# ProDoc_USB-C_Advanced_Power_Supply.net
KiCad netlist of a schematic drawn in EasyEDA Pro
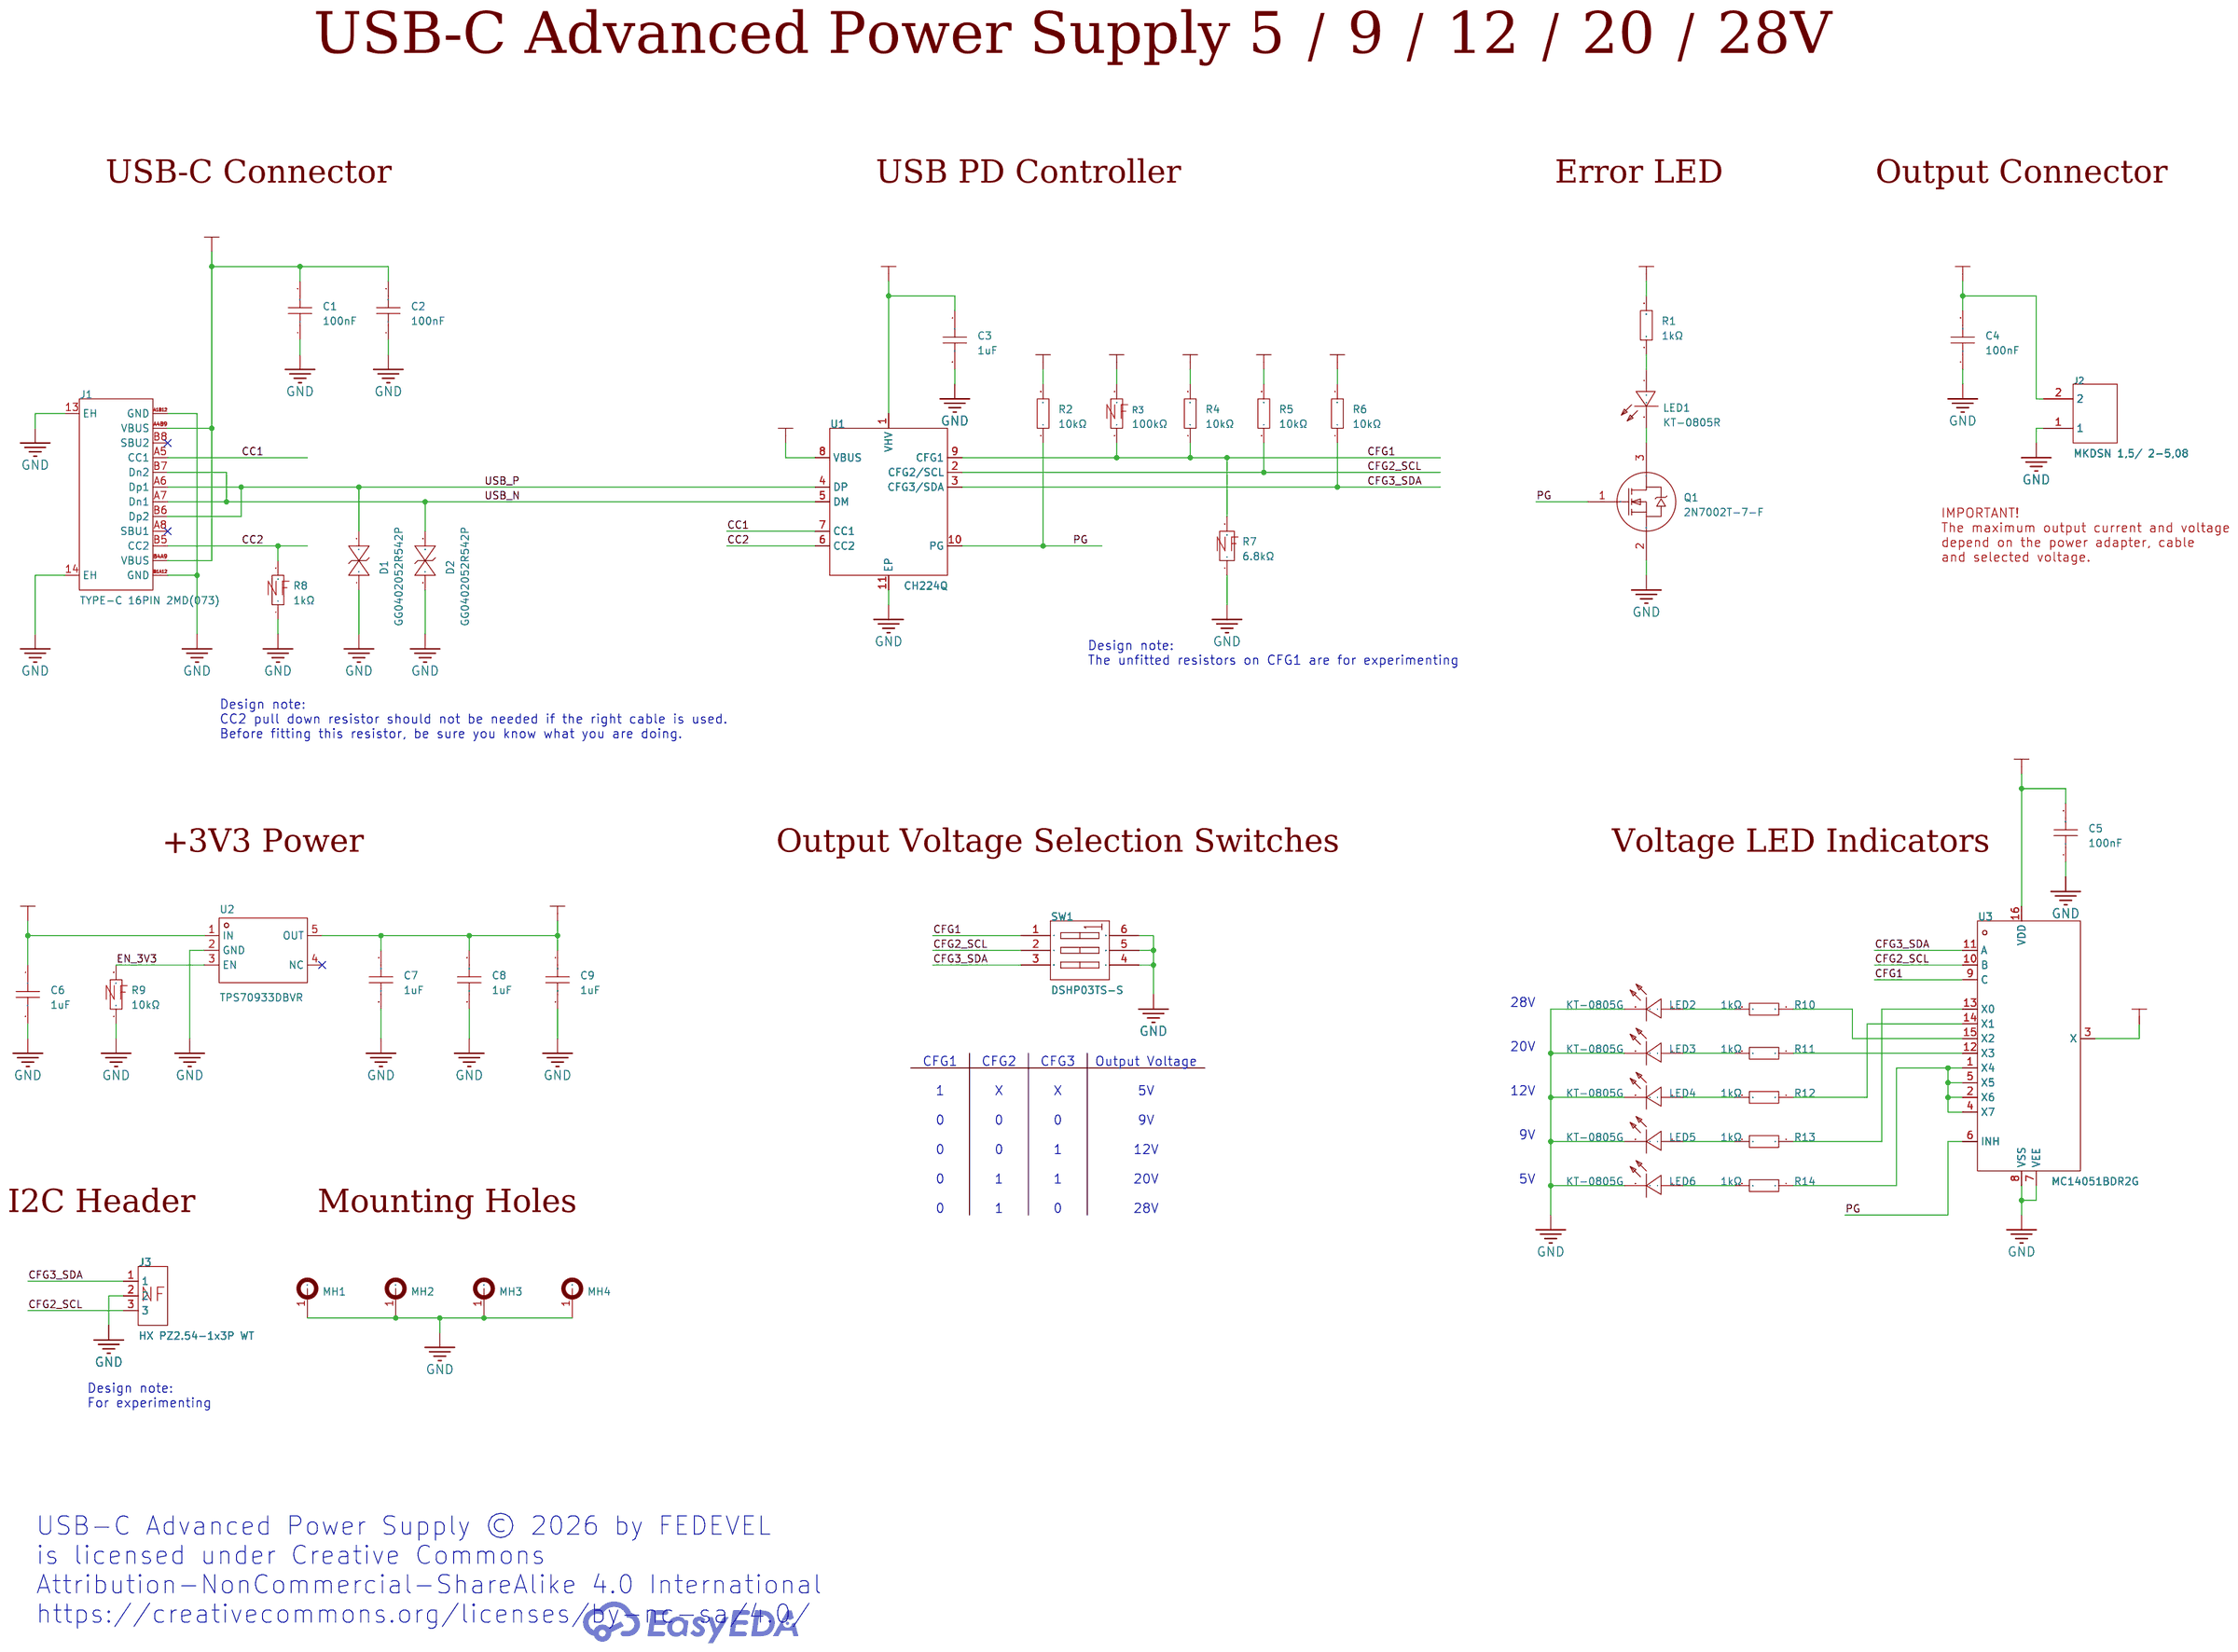
[diagram p0: schematic sheet]

(export (version "E")
  (design (tool "Eeschema 10.0.6"))
  (components
    (comp (ref "C1")
      (value "100nF")
      (footprint "easyedapro:C0402")
      (description "Capacitance:100nF Tolerance:±10% Tolerance:±10% Voltage Rating:50V Temperature Coefficient:X7R")
      (fields
        (field (name "Manufacturer Part") "CL05B104KB54PNC")
        (field (name "Manufacturer") "SAMSUNG(三星)")
      )
      (libsource (lib "easyedapro") (part "CL05B104KB54PNC"))
    )
    (comp (ref "C2")
      (value "100nF")
      (footprint "easyedapro:C0402")
      (description "Capacitance:100nF Tolerance:±10% Tolerance:±10% Voltage Rating:50V Temperature Coefficient:X7R")
      (fields
        (field (name "Manufacturer Part") "CL05B104KB54PNC")
        (field (name "Manufacturer") "SAMSUNG(三星)")
      )
      (libsource (lib "easyedapro") (part "CL05B104KB54PNC"))
    )
    (comp (ref "C3")
      (value "1uF")
      (footprint "easyedapro:C0603")
      (description "Capacitance:1uF Tolerance:±10% Tolerance:±10% Voltage Rating:50V Temperature Coefficient:X7R")
      (fields
        (field (name "Manufacturer Part") "CL10B105KB8NQNC")
        (field (name "Manufacturer") "SAMSUNG(三星)")
      )
      (libsource (lib "easyedapro") (part "CL10B105KB8NQNC"))
    )
    (comp (ref "C4")
      (value "100nF")
      (footprint "easyedapro:C0402")
      (description "Capacitance:100nF Tolerance:±10% Tolerance:±10% Voltage Rating:50V Temperature Coefficient:X7R")
      (fields
        (field (name "Manufacturer Part") "CL05B104KB54PNC")
        (field (name "Manufacturer") "SAMSUNG(三星)")
      )
      (libsource (lib "easyedapro") (part "CL05B104KB54PNC"))
    )
    (comp (ref "C5")
      (value "100nF")
      (footprint "easyedapro:C0402")
      (description "Capacitance:100nF Tolerance:±10% Tolerance:±10% Voltage Rating:50V Temperature Coefficient:X7R")
      (fields
        (field (name "Manufacturer Part") "CL05B104KB54PNC")
        (field (name "Manufacturer") "SAMSUNG(三星)")
      )
      (libsource (lib "easyedapro") (part "CL05B104KB54PNC"))
    )
    (comp (ref "C6")
      (value "1uF")
      (footprint "easyedapro:C0603")
      (description "Capacitance:1uF Tolerance:±10% Tolerance:±10% Voltage Rating:50V Temperature Coefficient:X7R")
      (fields
        (field (name "Manufacturer Part") "CL10B105KB8NQNC")
        (field (name "Manufacturer") "SAMSUNG(三星)")
      )
      (libsource (lib "easyedapro") (part "CL10B105KB8NQNC"))
    )
    (comp (ref "C7")
      (value "1uF")
      (footprint "easyedapro:C0603")
      (description "Capacitance:1uF Tolerance:±10% Tolerance:±10% Voltage Rating:50V Temperature Coefficient:X7R")
      (fields
        (field (name "Manufacturer Part") "CL10B105KB8NQNC")
        (field (name "Manufacturer") "SAMSUNG(三星)")
      )
      (libsource (lib "easyedapro") (part "CL10B105KB8NQNC"))
    )
    (comp (ref "C8")
      (value "1uF")
      (footprint "easyedapro:C0603")
      (description "Capacitance:1uF Tolerance:±10% Tolerance:±10% Voltage Rating:50V Temperature Coefficient:X7R")
      (fields
        (field (name "Manufacturer Part") "CL10B105KB8NQNC")
        (field (name "Manufacturer") "SAMSUNG(三星)")
      )
      (libsource (lib "easyedapro") (part "CL10B105KB8NQNC"))
    )
    (comp (ref "C9")
      (value "1uF")
      (footprint "easyedapro:C0603")
      (description "Capacitance:1uF Tolerance:±10% Tolerance:±10% Voltage Rating:50V Temperature Coefficient:X7R")
      (fields
        (field (name "Manufacturer Part") "CL10B105KB8NQNC")
        (field (name "Manufacturer") "SAMSUNG(三星)")
      )
      (libsource (lib "easyedapro") (part "CL10B105KB8NQNC"))
    )
    (comp (ref "D1")
      (value "GG0402052R542P")
      (footprint "easyedapro:D0402-BI")
      (fields (field (name "Manufacturer") "Kyocera AVX"))
      (libsource (lib "easyedapro") (part "GG0402052R542P"))
    )
    (comp (ref "D2")
      (value "GG0402052R542P")
      (footprint "easyedapro:D0402-BI")
      (fields (field (name "Manufacturer") "Kyocera AVX"))
      (libsource (lib "easyedapro") (part "GG0402052R542P"))
    )
    (comp (ref "J1")
      (value "TYPE-C 16PIN 2MD(073)")
      (footprint "easyedapro:USB-C-SMD_TYPE-C-16PIN-2MD-073")
      (fields (field (name "Manufacturer") "SHOU HAN(首韩)"))
      (libsource (lib "easyedapro") (part "TYPE-C 16PIN 2MD(073)"))
    )
    (comp (ref "J2")
      (value "MKDSN 1,5/ 2-5,08")
      (footprint "easyedapro:CONN-TH_2P-P5.08_1729128")
      (fields (field (name "Manufacturer") "Phoenix Contact(菲尼克斯)"))
      (libsource (lib "easyedapro") (part "MKDSN 1,5/ 2-5,08"))
    )
    (comp (ref "J3")
      (value "HX PZ2.54-1x3P WT")
      (footprint "easyedapro:HDR-SMD_3P-P2.54-H-M_KH-2.54PH-1X3P-L13.5-WT")
      (fields (field (name "Manufacturer") "hanxia(韩下)"))
      (libsource (lib "easyedapro") (part "HX PZ2.54-1X3P WT"))
    )
    (comp (ref "LED1")
      (value "KT-0805R")
      (footprint "easyedapro:LED0805-R-RD")
      (fields (field (name "Manufacturer") "KENTO"))
      (libsource (lib "easyedapro") (part "E6C0805UR"))
    )
    (comp (ref "LED2")
      (value "KT-0805G")
      (footprint "easyedapro:LED0805-R-RD")
      (fields (field (name "Manufacturer") "KENTO"))
      (libsource (lib "easyedapro") (part "0805G (Green)"))
    )
    (comp (ref "LED3")
      (value "KT-0805G")
      (footprint "easyedapro:LED0805-R-RD")
      (fields (field (name "Manufacturer") "KENTO"))
      (libsource (lib "easyedapro") (part "0805G (Green)"))
    )
    (comp (ref "LED4")
      (value "KT-0805G")
      (footprint "easyedapro:LED0805-R-RD")
      (fields (field (name "Manufacturer") "KENTO"))
      (libsource (lib "easyedapro") (part "0805G (Green)"))
    )
    (comp (ref "LED5")
      (value "KT-0805G")
      (footprint "easyedapro:LED0805-R-RD")
      (fields (field (name "Manufacturer") "KENTO"))
      (libsource (lib "easyedapro") (part "0805G (Green)"))
    )
    (comp (ref "LED6")
      (value "KT-0805G")
      (footprint "easyedapro:LED0805-R-RD")
      (fields (field (name "Manufacturer") "KENTO"))
      (libsource (lib "easyedapro") (part "0805G (Green)"))
    )
    (comp (ref "MH1")
      (value "~")
      (footprint "easyedapro:MH_7.5MMx2.7MM")
      (libsource (lib "easyedapro") (part "MH_7.5MMx2.7MM"))
    )
    (comp (ref "MH2")
      (value "~")
      (footprint "easyedapro:MH_7.5MMx2.7MM")
      (libsource (lib "easyedapro") (part "MH_7.5MMx2.7MM"))
    )
    (comp (ref "MH3")
      (value "~")
      (footprint "easyedapro:MH_7.5MMx2.7MM")
      (libsource (lib "easyedapro") (part "MH_7.5MMx2.7MM"))
    )
    (comp (ref "MH4")
      (value "~")
      (footprint "easyedapro:MH_7.5MMx2.7MM")
      (libsource (lib "easyedapro") (part "MH_7.5MMx2.7MM"))
    )
    (comp (ref "Q1")
      (value "2N7002T-7-F")
      (footprint "easyedapro:SOT-523-3_L1.6-W0.8-P1.00-LS1.6-BR")
      (fields (field (name "Manufacturer") "DIODES(美台)"))
      (libsource (lib "easyedapro") (part "2N7002T-7-F"))
    )
    (comp (ref "R1")
      (value "1kΩ")
      (footprint "easyedapro:R0402")
      (fields
        (field (name "Manufacturer Part") "0402WGF1001TCE")
        (field (name "Manufacturer") "UNI-ROYAL(厚声)")
      )
      (libsource (lib "easyedapro") (part "0402WGF1001TCE"))
    )
    (comp (ref "R2")
      (value "10kΩ")
      (footprint "easyedapro:R0402")
      (fields
        (field (name "Manufacturer Part") "0402WGF1002TCE")
        (field (name "Manufacturer") "UNI-ROYAL(厚声)")
      )
      (libsource (lib "easyedapro") (part "0402WGF1002TCE"))
    )
    (comp (ref "R3")
      (value "100kΩ")
      (footprint "easyedapro:R0402")
      (fields
        (field (name "Manufacturer Part") "0402WGF1003TCE")
        (field (name "Manufacturer") "UNI-ROYAL(厚声)")
      )
      (libsource (lib "easyedapro") (part "0402WGF1003TCE"))
    )
    (comp (ref "R4")
      (value "10kΩ")
      (footprint "easyedapro:R0402")
      (fields
        (field (name "Manufacturer Part") "0402WGF1002TCE")
        (field (name "Manufacturer") "UNI-ROYAL(厚声)")
      )
      (libsource (lib "easyedapro") (part "0402WGF1002TCE"))
    )
    (comp (ref "R5")
      (value "10kΩ")
      (footprint "easyedapro:R0402")
      (fields
        (field (name "Manufacturer Part") "0402WGF1002TCE")
        (field (name "Manufacturer") "UNI-ROYAL(厚声)")
      )
      (libsource (lib "easyedapro") (part "0402WGF1002TCE"))
    )
    (comp (ref "R6")
      (value "10kΩ")
      (footprint "easyedapro:R0402")
      (fields
        (field (name "Manufacturer Part") "0402WGF1002TCE")
        (field (name "Manufacturer") "UNI-ROYAL(厚声)")
      )
      (libsource (lib "easyedapro") (part "0402WGF1002TCE"))
    )
    (comp (ref "R7")
      (value "6.8kΩ")
      (footprint "easyedapro:R0402")
      (fields
        (field (name "Manufacturer Part") "NQ02WGF6801TCE")
        (field (name "Manufacturer") "UNI-ROYAL(厚声)")
      )
      (libsource (lib "easyedapro") (part "NQ02WGF6801TCE"))
    )
    (comp (ref "R8")
      (value "1kΩ")
      (footprint "easyedapro:R0402")
      (fields
        (field (name "Manufacturer Part") "0402WGF1001TCE")
        (field (name "Manufacturer") "UNI-ROYAL(厚声)")
      )
      (libsource (lib "easyedapro") (part "0402WGF1001TCE"))
    )
    (comp (ref "R9")
      (value "10kΩ")
      (footprint "easyedapro:R0402")
      (fields
        (field (name "Manufacturer Part") "0402WGF1002TCE")
        (field (name "Manufacturer") "UNI-ROYAL(厚声)")
      )
      (libsource (lib "easyedapro") (part "0402WGF1002TCE"))
    )
    (comp (ref "R10")
      (value "1kΩ")
      (footprint "easyedapro:R0402")
      (fields
        (field (name "Manufacturer Part") "0402WGF1001TCE")
        (field (name "Manufacturer") "UNI-ROYAL(厚声)")
      )
      (libsource (lib "easyedapro") (part "0402WGF1001TCE"))
    )
    (comp (ref "R11")
      (value "1kΩ")
      (footprint "easyedapro:R0402")
      (fields
        (field (name "Manufacturer Part") "0402WGF1001TCE")
        (field (name "Manufacturer") "UNI-ROYAL(厚声)")
      )
      (libsource (lib "easyedapro") (part "0402WGF1001TCE"))
    )
    (comp (ref "R12")
      (value "1kΩ")
      (footprint "easyedapro:R0402")
      (fields
        (field (name "Manufacturer Part") "0402WGF1001TCE")
        (field (name "Manufacturer") "UNI-ROYAL(厚声)")
      )
      (libsource (lib "easyedapro") (part "0402WGF1001TCE"))
    )
    (comp (ref "R13")
      (value "1kΩ")
      (footprint "easyedapro:R0402")
      (fields
        (field (name "Manufacturer Part") "0402WGF1001TCE")
        (field (name "Manufacturer") "UNI-ROYAL(厚声)")
      )
      (libsource (lib "easyedapro") (part "0402WGF1001TCE"))
    )
    (comp (ref "R14")
      (value "1kΩ")
      (footprint "easyedapro:R0402")
      (fields
        (field (name "Manufacturer Part") "0402WGF1001TCE")
        (field (name "Manufacturer") "UNI-ROYAL(厚声)")
      )
      (libsource (lib "easyedapro") (part "0402WGF1001TCE"))
    )
    (comp (ref "SW1")
      (value "DSHP03TS-S")
      (footprint "easyedapro:SW-SMD_DSHP03TS-S")
      (fields (field (name "Manufacturer") "XKB Connection(中国星坤)"))
      (libsource (lib "easyedapro") (part "DSHP03TS-S"))
    )
    (comp (ref "U1")
      (value "CH224Q")
      (footprint "easyedapro:DFN-10_L2.0-W2.0-P0.40-BL-EP")
      (fields (field (name "Manufacturer") "WCH(南京沁恒)"))
      (libsource (lib "easyedapro") (part "CH224Q-RF"))
    )
    (comp (ref "U2")
      (value "TPS70933DBVR")
      (footprint "easyedapro:SOT-23-5_L3.0-W1.7-P0.95-LS2.8-BR")
      (fields (field (name "Manufacturer") "TI(德州仪器)"))
      (libsource (lib "easyedapro") (part "TPS70933DBVR"))
    )
    (comp (ref "U3")
      (value "MC14051BDR2G")
      (footprint "easyedapro:SOIC-16_L9.9-W3.9-P1.27-LS6.0-BL_1")
      (fields (field (name "Manufacturer") "onsemi(安森美)"))
      (libsource (lib "easyedapro") (part "MC14051BDR2G-RF"))
    )
  )
  (nets
    (net (code "1") (name "+3V3") (class "Default")
      (node (ref "C5") (pin "2") (pinfunction "2_2") (pintype "input"))
      (node (ref "C7") (pin "1") (pinfunction "1_1") (pintype "unspecified"))
      (node (ref "C8") (pin "1") (pinfunction "1_1") (pintype "unspecified"))
      (node (ref "C9") (pin "1") (pinfunction "1_1") (pintype "unspecified"))
      (node (ref "R1") (pin "2") (pinfunction "2_2") (pintype "input"))
      (node (ref "R2") (pin "2") (pinfunction "2_2") (pintype "input"))
      (node (ref "R4") (pin "2") (pinfunction "2_2") (pintype "input"))
      (node (ref "R5") (pin "2") (pinfunction "2_2") (pintype "input"))
      (node (ref "R6") (pin "2") (pinfunction "2_2") (pintype "input"))
      (node (ref "U2") (pin "5") (pinfunction "OUT_5") (pintype "unspecified"))
      (node (ref "U3") (pin "16") (pinfunction "VDD_16") (pintype "unspecified"))
      (node (ref "U3") (pin "3") (pinfunction "X_3") (pintype "unspecified"))
    )
    (net (code "2") (name "+V_USB") (class "Default")
      (node (ref "C1") (pin "2") (pinfunction "2_2") (pintype "input"))
      (node (ref "C2") (pin "2") (pinfunction "2_2") (pintype "input"))
      (node (ref "C3") (pin "1") (pinfunction "1_1") (pintype "unspecified"))
      (node (ref "C4") (pin "2") (pinfunction "2_2") (pintype "input"))
      (node (ref "C6") (pin "1") (pinfunction "1_1") (pintype "unspecified"))
      (node (ref "J1") (pin "A4B9") (pinfunction "VBUS_A4B9") (pintype "unspecified"))
      (node (ref "J1") (pin "B4A9") (pinfunction "VBUS_B4A9") (pintype "unspecified"))
      (node (ref "J2") (pin "2") (pinfunction "2_2") (pintype "input"))
      (node (ref "R3") (pin "2") (pinfunction "2_2") (pintype "input"))
      (node (ref "U1") (pin "1") (pinfunction "VHV_1") (pintype "unspecified"))
      (node (ref "U1") (pin "8") (pinfunction "VBUS_8") (pintype "unspecified"))
      (node (ref "U2") (pin "1") (pinfunction "IN_1") (pintype "unspecified"))
    )
    (net (code "3") (name "/CC1") (class "Default")
      (node (ref "J1") (pin "A5") (pinfunction "CC1_A5") (pintype "unspecified"))
      (node (ref "U1") (pin "7") (pinfunction "CC1_7") (pintype "unspecified"))
    )
    (net (code "4") (name "/CC2") (class "Default")
      (node (ref "J1") (pin "B5") (pinfunction "CC2_B5") (pintype "unspecified"))
      (node (ref "R8") (pin "2") (pinfunction "2_2") (pintype "input"))
      (node (ref "U1") (pin "6") (pinfunction "CC2_6") (pintype "unspecified"))
    )
    (net (code "5") (name "/CFG1") (class "Default")
      (node (ref "R3") (pin "1") (pinfunction "1_1") (pintype "input"))
      (node (ref "R4") (pin "1") (pinfunction "1_1") (pintype "input"))
      (node (ref "R7") (pin "2") (pinfunction "2_2") (pintype "unspecified"))
      (node (ref "SW1") (pin "1") (pinfunction "1_1") (pintype "input"))
      (node (ref "U1") (pin "9") (pinfunction "CFG1_9") (pintype "unspecified"))
      (node (ref "U3") (pin "9") (pinfunction "C_9") (pintype "unspecified"))
    )
    (net (code "6") (name "/CFG2_SCL") (class "Default")
      (node (ref "J3") (pin "3") (pinfunction "3_3") (pintype "unspecified"))
      (node (ref "R5") (pin "1") (pinfunction "1_1") (pintype "input"))
      (node (ref "SW1") (pin "2") (pinfunction "2_2") (pintype "input"))
      (node (ref "U1") (pin "2") (pinfunction "CFG2/SCL_2") (pintype "unspecified"))
      (node (ref "U3") (pin "10") (pinfunction "B_10") (pintype "unspecified"))
    )
    (net (code "7") (name "/CFG3_SDA") (class "Default")
      (node (ref "J3") (pin "1") (pinfunction "1_1") (pintype "unspecified"))
      (node (ref "R6") (pin "1") (pinfunction "1_1") (pintype "input"))
      (node (ref "SW1") (pin "3") (pinfunction "3_3") (pintype "input"))
      (node (ref "U1") (pin "3") (pinfunction "CFG3/SDA_3") (pintype "unspecified"))
      (node (ref "U3") (pin "11") (pinfunction "A_11") (pintype "unspecified"))
    )
    (net (code "8") (name "/EN_3V3") (class "Default")
      (node (ref "R9") (pin "2") (pinfunction "2_2") (pintype "input"))
      (node (ref "U2") (pin "3") (pinfunction "EN_3") (pintype "unspecified"))
    )
    (net (code "9") (name "/PG") (class "Default")
      (node (ref "Q1") (pin "1") (pinfunction "G_1") (pintype "unspecified"))
      (node (ref "R2") (pin "1") (pinfunction "1_1") (pintype "input"))
      (node (ref "U1") (pin "10") (pinfunction "PG_10") (pintype "unspecified"))
      (node (ref "U3") (pin "6") (pinfunction "INH_6") (pintype "unspecified"))
    )
    (net (code "10") (name "/USB_N") (class "Default")
      (node (ref "D2") (pin "2") (pinfunction "2_2") (pintype "unspecified"))
      (node (ref "J1") (pin "A7") (pinfunction "Dn1_A7") (pintype "unspecified"))
      (node (ref "J1") (pin "B7") (pinfunction "Dn2_B7") (pintype "unspecified"))
      (node (ref "U1") (pin "5") (pinfunction "DM_5") (pintype "unspecified"))
    )
    (net (code "11") (name "/USB_P") (class "Default")
      (node (ref "D1") (pin "2") (pinfunction "2_2") (pintype "unspecified"))
      (node (ref "J1") (pin "A6") (pinfunction "Dp1_A6") (pintype "unspecified"))
      (node (ref "J1") (pin "B6") (pinfunction "Dp2_B6") (pintype "unspecified"))
      (node (ref "U1") (pin "4") (pinfunction "DP_4") (pintype "unspecified"))
    )
    (net (code "12") (name "GND") (class "Default")
      (node (ref "C1") (pin "1") (pinfunction "1_1") (pintype "input"))
      (node (ref "C2") (pin "1") (pinfunction "1_1") (pintype "input"))
      (node (ref "C3") (pin "2") (pinfunction "2_2") (pintype "unspecified"))
      (node (ref "C4") (pin "1") (pinfunction "1_1") (pintype "input"))
      (node (ref "C5") (pin "1") (pinfunction "1_1") (pintype "input"))
      (node (ref "C6") (pin "2") (pinfunction "2_2") (pintype "unspecified"))
      (node (ref "C7") (pin "2") (pinfunction "2_2") (pintype "unspecified"))
      (node (ref "C8") (pin "2") (pinfunction "2_2") (pintype "unspecified"))
      (node (ref "C9") (pin "2") (pinfunction "2_2") (pintype "unspecified"))
      (node (ref "D1") (pin "1") (pinfunction "1_1") (pintype "unspecified"))
      (node (ref "D2") (pin "1") (pinfunction "1_1") (pintype "unspecified"))
      (node (ref "J1") (pin "13") (pinfunction "EH_13") (pintype "unspecified"))
      (node (ref "J1") (pin "14") (pinfunction "EH_14") (pintype "unspecified"))
      (node (ref "J1") (pin "A1B12") (pinfunction "GND_A1B12") (pintype "unspecified"))
      (node (ref "J1") (pin "B1A12") (pinfunction "GND_B1A12") (pintype "unspecified"))
      (node (ref "J2") (pin "1") (pinfunction "1_1") (pintype "input"))
      (node (ref "J3") (pin "2") (pinfunction "2_2") (pintype "unspecified"))
      (node (ref "LED2") (pin "2") (pinfunction "K_2") (pintype "unspecified"))
      (node (ref "LED3") (pin "2") (pinfunction "K_2") (pintype "unspecified"))
      (node (ref "LED4") (pin "2") (pinfunction "K_2") (pintype "unspecified"))
      (node (ref "LED5") (pin "2") (pinfunction "K_2") (pintype "unspecified"))
      (node (ref "LED6") (pin "2") (pinfunction "K_2") (pintype "unspecified"))
      (node (ref "MH1") (pin "1") (pinfunction "1_1") (pintype "input"))
      (node (ref "MH2") (pin "1") (pinfunction "1_1") (pintype "input"))
      (node (ref "MH3") (pin "1") (pinfunction "1_1") (pintype "input"))
      (node (ref "MH4") (pin "1") (pinfunction "1_1") (pintype "input"))
      (node (ref "Q1") (pin "2") (pinfunction "S_2") (pintype "unspecified"))
      (node (ref "R7") (pin "1") (pinfunction "1_1") (pintype "unspecified"))
      (node (ref "R8") (pin "1") (pinfunction "1_1") (pintype "input"))
      (node (ref "R9") (pin "1") (pinfunction "1_1") (pintype "input"))
      (node (ref "SW1") (pin "4") (pinfunction "4_4") (pintype "input"))
      (node (ref "SW1") (pin "5") (pinfunction "5_5") (pintype "input"))
      (node (ref "SW1") (pin "6") (pinfunction "6_6") (pintype "input"))
      (node (ref "U1") (pin "11") (pinfunction "EP_11") (pintype "unspecified"))
      (node (ref "U2") (pin "2") (pinfunction "GND_2") (pintype "unspecified"))
      (node (ref "U3") (pin "7") (pinfunction "VEE_7") (pintype "unspecified"))
      (node (ref "U3") (pin "8") (pinfunction "VSS_8") (pintype "unspecified"))
    )
    (net (code "13") (name "Net-(LED1-A)") (class "Default")
      (node (ref "LED1") (pin "1") (pinfunction "A_1") (pintype "unspecified"))
      (node (ref "R1") (pin "1") (pinfunction "1_1") (pintype "input"))
    )
    (net (code "14") (name "Net-(LED1-K)") (class "Default")
      (node (ref "LED1") (pin "2") (pinfunction "K_2") (pintype "unspecified"))
      (node (ref "Q1") (pin "3") (pinfunction "D_3") (pintype "unspecified"))
    )
    (net (code "15") (name "Net-(LED2-A)") (class "Default")
      (node (ref "LED2") (pin "1") (pinfunction "A_1") (pintype "unspecified"))
      (node (ref "R10") (pin "2") (pinfunction "2_2") (pintype "input"))
    )
    (net (code "16") (name "Net-(LED3-A)") (class "Default")
      (node (ref "LED3") (pin "1") (pinfunction "A_1") (pintype "unspecified"))
      (node (ref "R11") (pin "2") (pinfunction "2_2") (pintype "input"))
    )
    (net (code "17") (name "Net-(LED4-A)") (class "Default")
      (node (ref "LED4") (pin "1") (pinfunction "A_1") (pintype "unspecified"))
      (node (ref "R12") (pin "2") (pinfunction "2_2") (pintype "input"))
    )
    (net (code "18") (name "Net-(LED5-A)") (class "Default")
      (node (ref "LED5") (pin "1") (pinfunction "A_1") (pintype "unspecified"))
      (node (ref "R13") (pin "2") (pinfunction "2_2") (pintype "input"))
    )
    (net (code "19") (name "Net-(LED6-A)") (class "Default")
      (node (ref "LED6") (pin "1") (pinfunction "A_1") (pintype "unspecified"))
      (node (ref "R14") (pin "2") (pinfunction "2_2") (pintype "input"))
    )
    (net (code "20") (name "Net-(U3-X0)") (class "Default")
      (node (ref "R13") (pin "1") (pinfunction "1_1") (pintype "input"))
      (node (ref "U3") (pin "13") (pinfunction "X0_13") (pintype "unspecified"))
    )
    (net (code "21") (name "Net-(U3-X1)") (class "Default")
      (node (ref "R12") (pin "1") (pinfunction "1_1") (pintype "input"))
      (node (ref "U3") (pin "14") (pinfunction "X1_14") (pintype "unspecified"))
    )
    (net (code "22") (name "Net-(U3-X2)") (class "Default")
      (node (ref "R10") (pin "1") (pinfunction "1_1") (pintype "input"))
      (node (ref "U3") (pin "15") (pinfunction "X2_15") (pintype "unspecified"))
    )
    (net (code "23") (name "Net-(U3-X3)") (class "Default")
      (node (ref "R11") (pin "1") (pinfunction "1_1") (pintype "input"))
      (node (ref "U3") (pin "12") (pinfunction "X3_12") (pintype "unspecified"))
    )
    (net (code "24") (name "Net-(U3-X4)") (class "Default")
      (node (ref "R14") (pin "1") (pinfunction "1_1") (pintype "input"))
      (node (ref "U3") (pin "1") (pinfunction "X4_1") (pintype "unspecified"))
      (node (ref "U3") (pin "2") (pinfunction "X6_2") (pintype "unspecified"))
      (node (ref "U3") (pin "4") (pinfunction "X7_4") (pintype "unspecified"))
      (node (ref "U3") (pin "5") (pinfunction "X5_5") (pintype "unspecified"))
    )
    (net (code "25") (name "unconnected-(J1-SBU1-PadA8)") (class "Default")
      (node (ref "J1") (pin "A8") (pinfunction "SBU1_A8") (pintype "unspecified+no_connect"))
    )
    (net (code "26") (name "unconnected-(J1-SBU2-PadB8)") (class "Default")
      (node (ref "J1") (pin "B8") (pinfunction "SBU2_B8") (pintype "unspecified+no_connect"))
    )
    (net (code "27") (name "unconnected-(U2-NC-Pad4)") (class "Default")
      (node (ref "U2") (pin "4") (pinfunction "NC_4") (pintype "unspecified+no_connect"))
    )
  )
)
